# SK3000v5_LOGO_VIAS.net
KiCad netlist of a schematic drawn in EAGLE
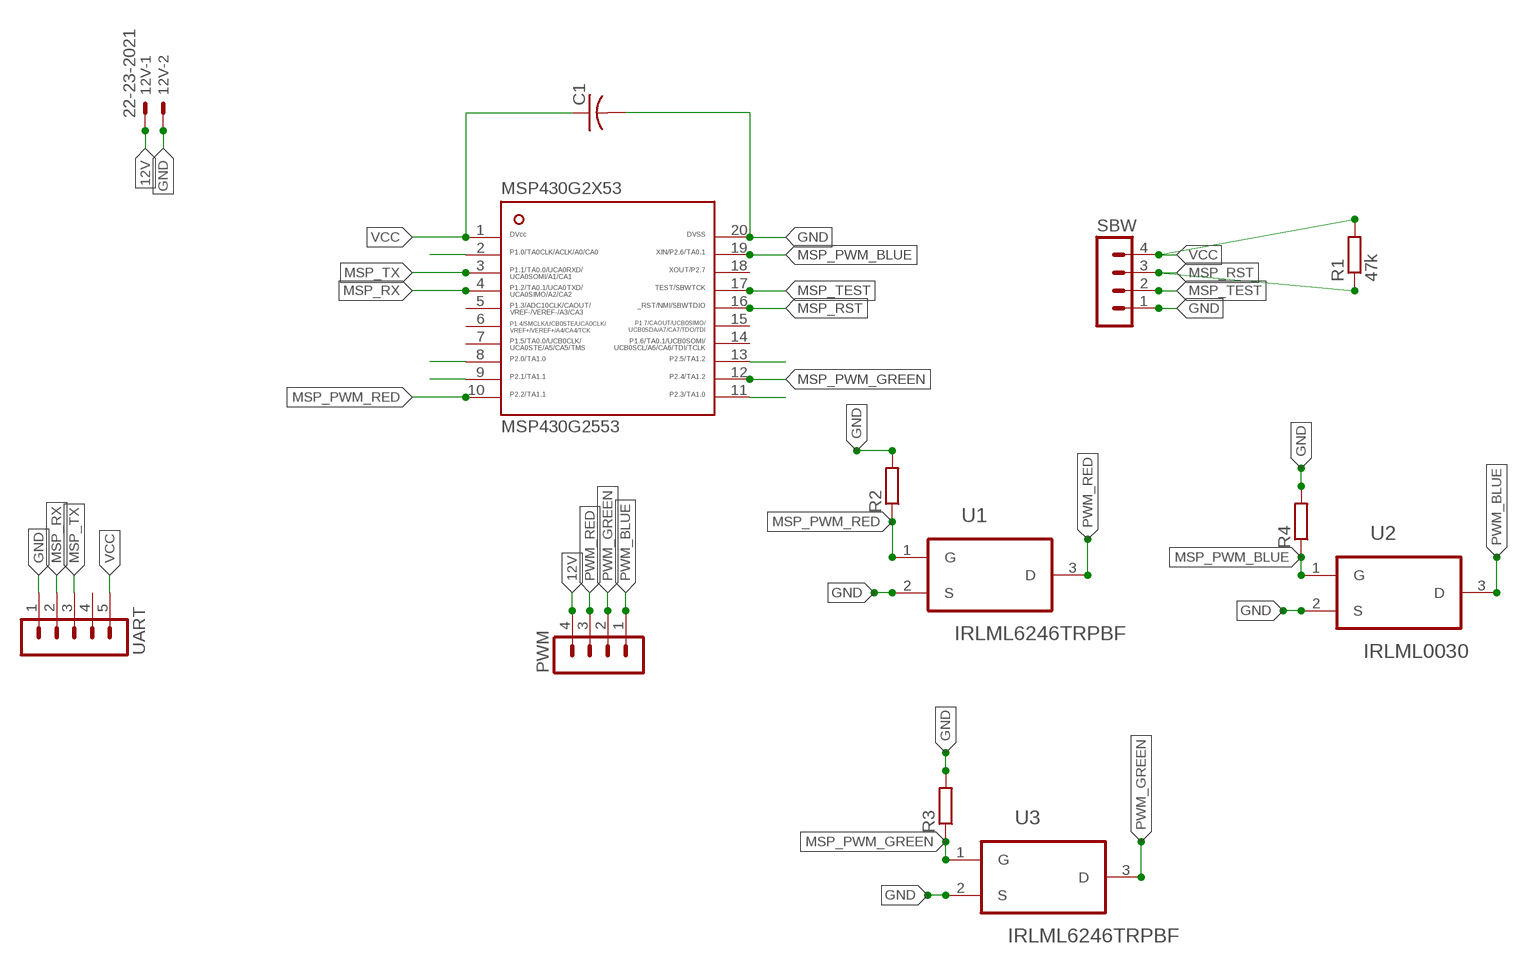
[diagram p0: schematic, sheet 1]

(export (version "E")
  (design (tool "Eeschema 10.0.6"))
  (components
    (comp (ref "12V")
      (value "22-23-2021")
      (footprint "eagle-import:22-23-2021")
      (fields (field (name "MF") "MOLEX"))
      (libsource (lib "eagle-import") (part "22-23-2021"))
    )
    (comp (ref "C1")
      (value "C-USC0603")
      (footprint "eagle-import:C0603")
      (libsource (lib "eagle-import") (part "C-USC0603"))
    )
    (comp (ref "MSP430G2553")
      (value "MSP430G2X53-20PW20")
      (footprint "eagle-import:PW20")
      (libsource (lib "eagle-import") (part "MSP430G2X53-20PW20"))
    )
    (comp (ref "PWM")
      (value "MA04-1")
      (footprint "eagle-import:MA04-1")
      (libsource (lib "eagle-import") (part "MA04-1"))
    )
    (comp (ref "R1")
      (value "47k")
      (footprint "eagle-import:R0603")
      (libsource (lib "eagle-import") (part "R-EU_R0603"))
    )
    (comp (ref "R2")
      (value "R-EU_R0603")
      (footprint "eagle-import:R0603")
      (libsource (lib "eagle-import") (part "R-EU_R0603"))
    )
    (comp (ref "R3")
      (value "R-EU_R0603")
      (footprint "eagle-import:R0603")
      (libsource (lib "eagle-import") (part "R-EU_R0603"))
    )
    (comp (ref "R4")
      (value "R-EU_R0603")
      (footprint "eagle-import:R0603")
      (libsource (lib "eagle-import") (part "R-EU_R0603"))
    )
    (comp (ref "SBW")
      (value "MA04-1")
      (footprint "eagle-import:MA04-1")
      (libsource (lib "eagle-import") (part "MA04-1"))
    )
    (comp (ref "U1")
      (value "IRLML6246TRPBF")
      (footprint "eagle-import:SOT95P240X112-3N")
      (libsource (lib "eagle-import") (part "IRLML6246TRPBF"))
    )
    (comp (ref "U2")
      (value "IRLML0030")
      (footprint "eagle-import:SOT95P240X112-3N")
      (fields (field (name "MPN") "IRLML6246TRPBF"))
      (libsource (lib "eagle-import") (part "IRLML6246TRPBF"))
    )
    (comp (ref "U3")
      (value "IRLML6246TRPBF")
      (footprint "eagle-import:SOT95P240X112-3N")
      (libsource (lib "eagle-import") (part "IRLML6246TRPBF"))
    )
    (comp (ref "UART")
      (value "MA05-1")
      (footprint "eagle-import:MA05-1")
      (libsource (lib "eagle-import") (part "MA05-1"))
    )
  )
  (nets
    (net (code "1") (name "12V") (class "Default")
      (node (ref "12V") (pin "1") (pinfunction "S_1") (pintype "passive"))
      (node (ref "PWM") (pin "4") (pinfunction "4_4") (pintype "passive"))
    )
    (net (code "2") (name "GND") (class "Default")
      (node (ref "12V") (pin "2") (pinfunction "S_2") (pintype "passive"))
      (node (ref "C1") (pin "2") (pinfunction "2_2") (pintype "passive"))
      (node (ref "MSP430G2553") (pin "20") (pinfunction "20_20") (pintype "bidirectional"))
      (node (ref "R2") (pin "2") (pinfunction "2_2") (pintype "passive"))
      (node (ref "R3") (pin "2") (pinfunction "2_2") (pintype "passive"))
      (node (ref "R4") (pin "2") (pinfunction "2_2") (pintype "passive"))
      (node (ref "SBW") (pin "1") (pinfunction "1_1") (pintype "passive"))
      (node (ref "U1") (pin "2") (pinfunction "S_2") (pintype "passive"))
      (node (ref "U2") (pin "2") (pinfunction "S_2") (pintype "passive"))
      (node (ref "U3") (pin "2") (pinfunction "S_2") (pintype "passive"))
      (node (ref "UART") (pin "1") (pinfunction "1_1") (pintype "passive"))
    )
    (net (code "3") (name "MSP_PWM_BLUE") (class "Default")
      (node (ref "MSP430G2553") (pin "19") (pinfunction "19_19") (pintype "bidirectional"))
      (node (ref "R4") (pin "1") (pinfunction "1_1") (pintype "passive"))
      (node (ref "U2") (pin "1") (pinfunction "G_1") (pintype "input"))
    )
    (net (code "4") (name "MSP_PWM_GREEN") (class "Default")
      (node (ref "MSP430G2553") (pin "12") (pinfunction "12_12") (pintype "bidirectional"))
      (node (ref "R3") (pin "1") (pinfunction "1_1") (pintype "passive"))
      (node (ref "U3") (pin "1") (pinfunction "G_1") (pintype "input"))
    )
    (net (code "5") (name "MSP_PWM_RED") (class "Default")
      (node (ref "MSP430G2553") (pin "10") (pinfunction "10_10") (pintype "bidirectional"))
      (node (ref "R2") (pin "1") (pinfunction "1_1") (pintype "passive"))
      (node (ref "U1") (pin "1") (pinfunction "G_1") (pintype "input"))
    )
    (net (code "6") (name "MSP_RST") (class "Default")
      (node (ref "MSP430G2553") (pin "16") (pinfunction "16_16") (pintype "bidirectional"))
      (node (ref "R1") (pin "1") (pinfunction "1_1") (pintype "passive"))
      (node (ref "SBW") (pin "3") (pinfunction "3_3") (pintype "passive"))
    )
    (net (code "7") (name "MSP_RX") (class "Default")
      (node (ref "MSP430G2553") (pin "4") (pinfunction "4_4") (pintype "bidirectional"))
      (node (ref "UART") (pin "2") (pinfunction "2_2") (pintype "passive"))
    )
    (net (code "8") (name "MSP_TEST") (class "Default")
      (node (ref "MSP430G2553") (pin "17") (pinfunction "17_17") (pintype "bidirectional"))
      (node (ref "SBW") (pin "2") (pinfunction "2_2") (pintype "passive"))
    )
    (net (code "9") (name "MSP_TX") (class "Default")
      (node (ref "MSP430G2553") (pin "3") (pinfunction "3_3") (pintype "bidirectional"))
      (node (ref "UART") (pin "3") (pinfunction "3_3") (pintype "passive"))
    )
    (net (code "10") (name "PWM_BLUE") (class "Default")
      (node (ref "PWM") (pin "1") (pinfunction "1_1") (pintype "passive"))
      (node (ref "U2") (pin "3") (pinfunction "D_3") (pintype "output"))
    )
    (net (code "11") (name "PWM_GREEN") (class "Default")
      (node (ref "PWM") (pin "2") (pinfunction "2_2") (pintype "passive"))
      (node (ref "U3") (pin "3") (pinfunction "D_3") (pintype "output"))
    )
    (net (code "12") (name "PWM_RED") (class "Default")
      (node (ref "PWM") (pin "3") (pinfunction "3_3") (pintype "passive"))
      (node (ref "U1") (pin "3") (pinfunction "D_3") (pintype "output"))
    )
    (net (code "13") (name "VCC") (class "Default")
      (node (ref "C1") (pin "1") (pinfunction "1_1") (pintype "passive"))
      (node (ref "MSP430G2553") (pin "1") (pinfunction "1_1") (pintype "bidirectional"))
      (node (ref "R1") (pin "2") (pinfunction "2_2") (pintype "passive"))
      (node (ref "SBW") (pin "4") (pinfunction "4_4") (pintype "passive"))
      (node (ref "UART") (pin "5") (pinfunction "5_5") (pintype "passive"))
    )
    (net (code "14") (name "unconnected-(MSP430G2553-Pad2)") (class "Default")
      (node (ref "MSP430G2553") (pin "2") (pinfunction "2_2") (pintype "bidirectional"))
    )
    (net (code "15") (name "unconnected-(MSP430G2553-Pad5)") (class "Default")
      (node (ref "MSP430G2553") (pin "5") (pinfunction "5_5") (pintype "bidirectional"))
    )
    (net (code "16") (name "unconnected-(MSP430G2553-Pad6)") (class "Default")
      (node (ref "MSP430G2553") (pin "6") (pinfunction "6_6") (pintype "bidirectional"))
    )
    (net (code "17") (name "unconnected-(MSP430G2553-Pad7)") (class "Default")
      (node (ref "MSP430G2553") (pin "7") (pinfunction "7_7") (pintype "bidirectional"))
    )
    (net (code "18") (name "unconnected-(MSP430G2553-Pad8)") (class "Default")
      (node (ref "MSP430G2553") (pin "8") (pinfunction "8_8") (pintype "bidirectional"))
    )
    (net (code "19") (name "unconnected-(MSP430G2553-Pad9)") (class "Default")
      (node (ref "MSP430G2553") (pin "9") (pinfunction "9_9") (pintype "bidirectional"))
    )
    (net (code "20") (name "unconnected-(MSP430G2553-Pad11)") (class "Default")
      (node (ref "MSP430G2553") (pin "11") (pinfunction "11_11") (pintype "bidirectional"))
    )
    (net (code "21") (name "unconnected-(MSP430G2553-Pad13)") (class "Default")
      (node (ref "MSP430G2553") (pin "13") (pinfunction "13_13") (pintype "bidirectional"))
    )
    (net (code "22") (name "unconnected-(MSP430G2553-Pad14)") (class "Default")
      (node (ref "MSP430G2553") (pin "14") (pinfunction "14_14") (pintype "bidirectional"))
    )
    (net (code "23") (name "unconnected-(MSP430G2553-Pad15)") (class "Default")
      (node (ref "MSP430G2553") (pin "15") (pinfunction "15_15") (pintype "bidirectional"))
    )
    (net (code "24") (name "unconnected-(MSP430G2553-Pad18)") (class "Default")
      (node (ref "MSP430G2553") (pin "18") (pinfunction "18_18") (pintype "bidirectional"))
    )
    (net (code "25") (name "unconnected-(UART-Pad4)") (class "Default")
      (node (ref "UART") (pin "4") (pinfunction "4_4") (pintype "passive"))
    )
  )
)
